# COMS0003_DTMF.net
KiCad netlist of a schematic drawn in Altium Designer
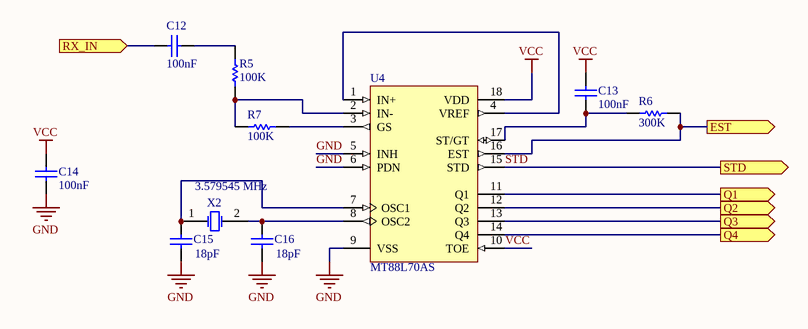
[diagram p0: COMS0003_DTMF.SchDoc]

(export (version "E")
  (design (tool "Eeschema 10.0.6"))
  (components
    (comp (ref "C12")
      (value "100nF")
      (footprint "CAPC2012M")
      (description "Capacitor")
      (fields (field (name "Comment") "Cap") (field (name "PUBLISHER") "Altium Limited"))
      (libsource (lib "Miscellaneous Devices") (part "Cap"))
    )
    (comp (ref "C13")
      (value "100nF")
      (footprint "CAPC2012M")
      (description "Capacitor")
      (fields (field (name "Comment") "Cap") (field (name "PUBLISHER") "Altium Limited"))
      (libsource (lib "Miscellaneous Devices") (part "Cap"))
    )
    (comp (ref "C14")
      (value "100nF")
      (footprint "CAPC2012M")
      (description "Capacitor")
      (fields (field (name "Comment") "Cap") (field (name "PUBLISHER") "Altium Limited"))
      (libsource (lib "Miscellaneous Devices") (part "Cap"))
    )
    (comp (ref "C15")
      (value "18pF")
      (footprint "CAPC2012M")
      (description "Capacitor")
      (fields (field (name "Comment") "Cap") (field (name "PUBLISHER") "Altium Limited"))
      (libsource (lib "Miscellaneous Devices") (part "Cap"))
    )
    (comp (ref "C16")
      (value "18pF")
      (footprint "CAPC2012M")
      (description "Capacitor")
      (fields (field (name "Comment") "Cap") (field (name "PUBLISHER") "Altium Limited"))
      (libsource (lib "Miscellaneous Devices") (part "Cap"))
    )
    (comp (ref "R5")
      (value "100K")
      (footprint "RESC2012M")
      (description "Resistor")
      (fields (field (name "Comment") "Res1") (field (name "PUBLISHER") "Altium Limited"))
      (libsource (lib "Miscellaneous Devices") (part "Res1"))
    )
    (comp (ref "R6")
      (value "300K")
      (footprint "RESC2012M")
      (description "Resistor")
      (fields (field (name "Comment") "Res1") (field (name "PUBLISHER") "Altium Limited"))
      (libsource (lib "Miscellaneous Devices") (part "Res1"))
    )
    (comp (ref "R7")
      (value "100K")
      (footprint "RESC2012M")
      (description "Resistor")
      (fields (field (name "Comment") "Res1") (field (name "PUBLISHER") "Altium Limited"))
      (libsource (lib "Miscellaneous Devices") (part "Res1"))
    )
    (comp (ref "U4")
      (value "MT88L70AS")
      (footprint "SOIC18_N")
      (description "3 Volt Integrated DTMF Receiver")
      (fields (field (name "PUBLISHER") "Altium Limited"))
      (libsource (lib "Zarlink Comm DTMF Receiver") (part "MT88L70AS"))
    )
    (comp (ref "X2")
      (value "3.579545 MHz")
      (footprint "CSM-7")
      (description "Crystal Oscillator")
      (fields (field (name "PUBLISHER") "Altium Limited"))
      (libsource (lib "ECS Crystal Oscillator") (part "ECS-110-S-5P"))
    )
  )
  (nets
    (net (code "1") (name "/EST") (class "Default")
      (node (ref "R6") (pin "1") (pinfunction "1_1") (pintype "passive"))
      (node (ref "U4") (pin "16") (pinfunction "EST_16") (pintype "output"))
    )
    (net (code "2") (name "/Q1") (class "Default")
      (node (ref "U4") (pin "11") (pinfunction "Q1_11") (pintype "tri_state"))
    )
    (net (code "3") (name "/Q2") (class "Default")
      (node (ref "U4") (pin "12") (pinfunction "Q2_12") (pintype "tri_state"))
    )
    (net (code "4") (name "/Q3") (class "Default")
      (node (ref "U4") (pin "13") (pinfunction "Q3_13") (pintype "tri_state"))
    )
    (net (code "5") (name "/Q4") (class "Default")
      (node (ref "U4") (pin "14") (pinfunction "Q4_14") (pintype "tri_state"))
    )
    (net (code "6") (name "/RX_IN") (class "Default")
      (node (ref "C12") (pin "2") (pinfunction "2_2") (pintype "passive"))
    )
    (net (code "7") (name "/STD") (class "Default")
      (node (ref "U4") (pin "15") (pinfunction "STD_15") (pintype "output"))
    )
    (net (code "8") (name "GND") (class "Default")
      (node (ref "C14") (pin "2") (pinfunction "2_2") (pintype "passive"))
      (node (ref "C15") (pin "2") (pinfunction "2_2") (pintype "passive"))
      (node (ref "C16") (pin "2") (pinfunction "2_2") (pintype "passive"))
      (node (ref "U4") (pin "5") (pinfunction "INH_5") (pintype "input"))
      (node (ref "U4") (pin "6") (pinfunction "PDN_6") (pintype "input"))
      (node (ref "U4") (pin "9") (pinfunction "VSS_9") (pintype "power_in"))
    )
    (net (code "9") (name "Net-(C12-Pad1)") (class "Default")
      (node (ref "C12") (pin "1") (pinfunction "1_1") (pintype "passive"))
      (node (ref "R5") (pin "2") (pinfunction "2_2") (pintype "passive"))
    )
    (net (code "10") (name "Net-(U4-GS)") (class "Default")
      (node (ref "R7") (pin "1") (pinfunction "1_1") (pintype "passive"))
      (node (ref "U4") (pin "3") (pinfunction "GS_3") (pintype "output"))
    )
    (net (code "11") (name "Net-(U4-IN+)") (class "Default")
      (node (ref "U4") (pin "1") (pinfunction "IN+_1") (pintype "input"))
      (node (ref "U4") (pin "4") (pinfunction "VREF_4") (pintype "output"))
    )
    (net (code "12") (name "Net-(U4-IN-)") (class "Default")
      (node (ref "R5") (pin "1") (pinfunction "1_1") (pintype "passive"))
      (node (ref "R7") (pin "2") (pinfunction "2_2") (pintype "passive"))
      (node (ref "U4") (pin "2") (pinfunction "IN-_2") (pintype "input"))
    )
    (net (code "13") (name "Net-(U4-OSC1)") (class "Default")
      (node (ref "C15") (pin "1") (pinfunction "1_1") (pintype "passive"))
      (node (ref "U4") (pin "7") (pinfunction "OSC1_7") (pintype "input"))
      (node (ref "X2") (pin "1") (pinfunction "OSC1_1") (pintype "passive"))
    )
    (net (code "14") (name "Net-(U4-OSC2)") (class "Default")
      (node (ref "C16") (pin "1") (pinfunction "1_1") (pintype "passive"))
      (node (ref "U4") (pin "8") (pinfunction "OSC2_8") (pintype "output"))
      (node (ref "X2") (pin "2") (pinfunction "OSC2_2") (pintype "passive"))
    )
    (net (code "15") (name "Net-(U4-ST{slash}GT)") (class "Default")
      (node (ref "C13") (pin "1") (pinfunction "1_1") (pintype "passive"))
      (node (ref "R6") (pin "2") (pinfunction "2_2") (pintype "passive"))
      (node (ref "U4") (pin "17") (pinfunction "ST/GT_17") (pintype "bidirectional"))
    )
    (net (code "16") (name "VCC") (class "Default")
      (node (ref "C13") (pin "2") (pinfunction "2_2") (pintype "passive"))
      (node (ref "C14") (pin "1") (pinfunction "1_1") (pintype "passive"))
      (node (ref "U4") (pin "10") (pinfunction "TOE_10") (pintype "input"))
      (node (ref "U4") (pin "18") (pinfunction "VDD_18") (pintype "power_in"))
    )
  )
)
